# C-metr_digital.net
KiCad netlist of a schematic drawn in Altium Designer
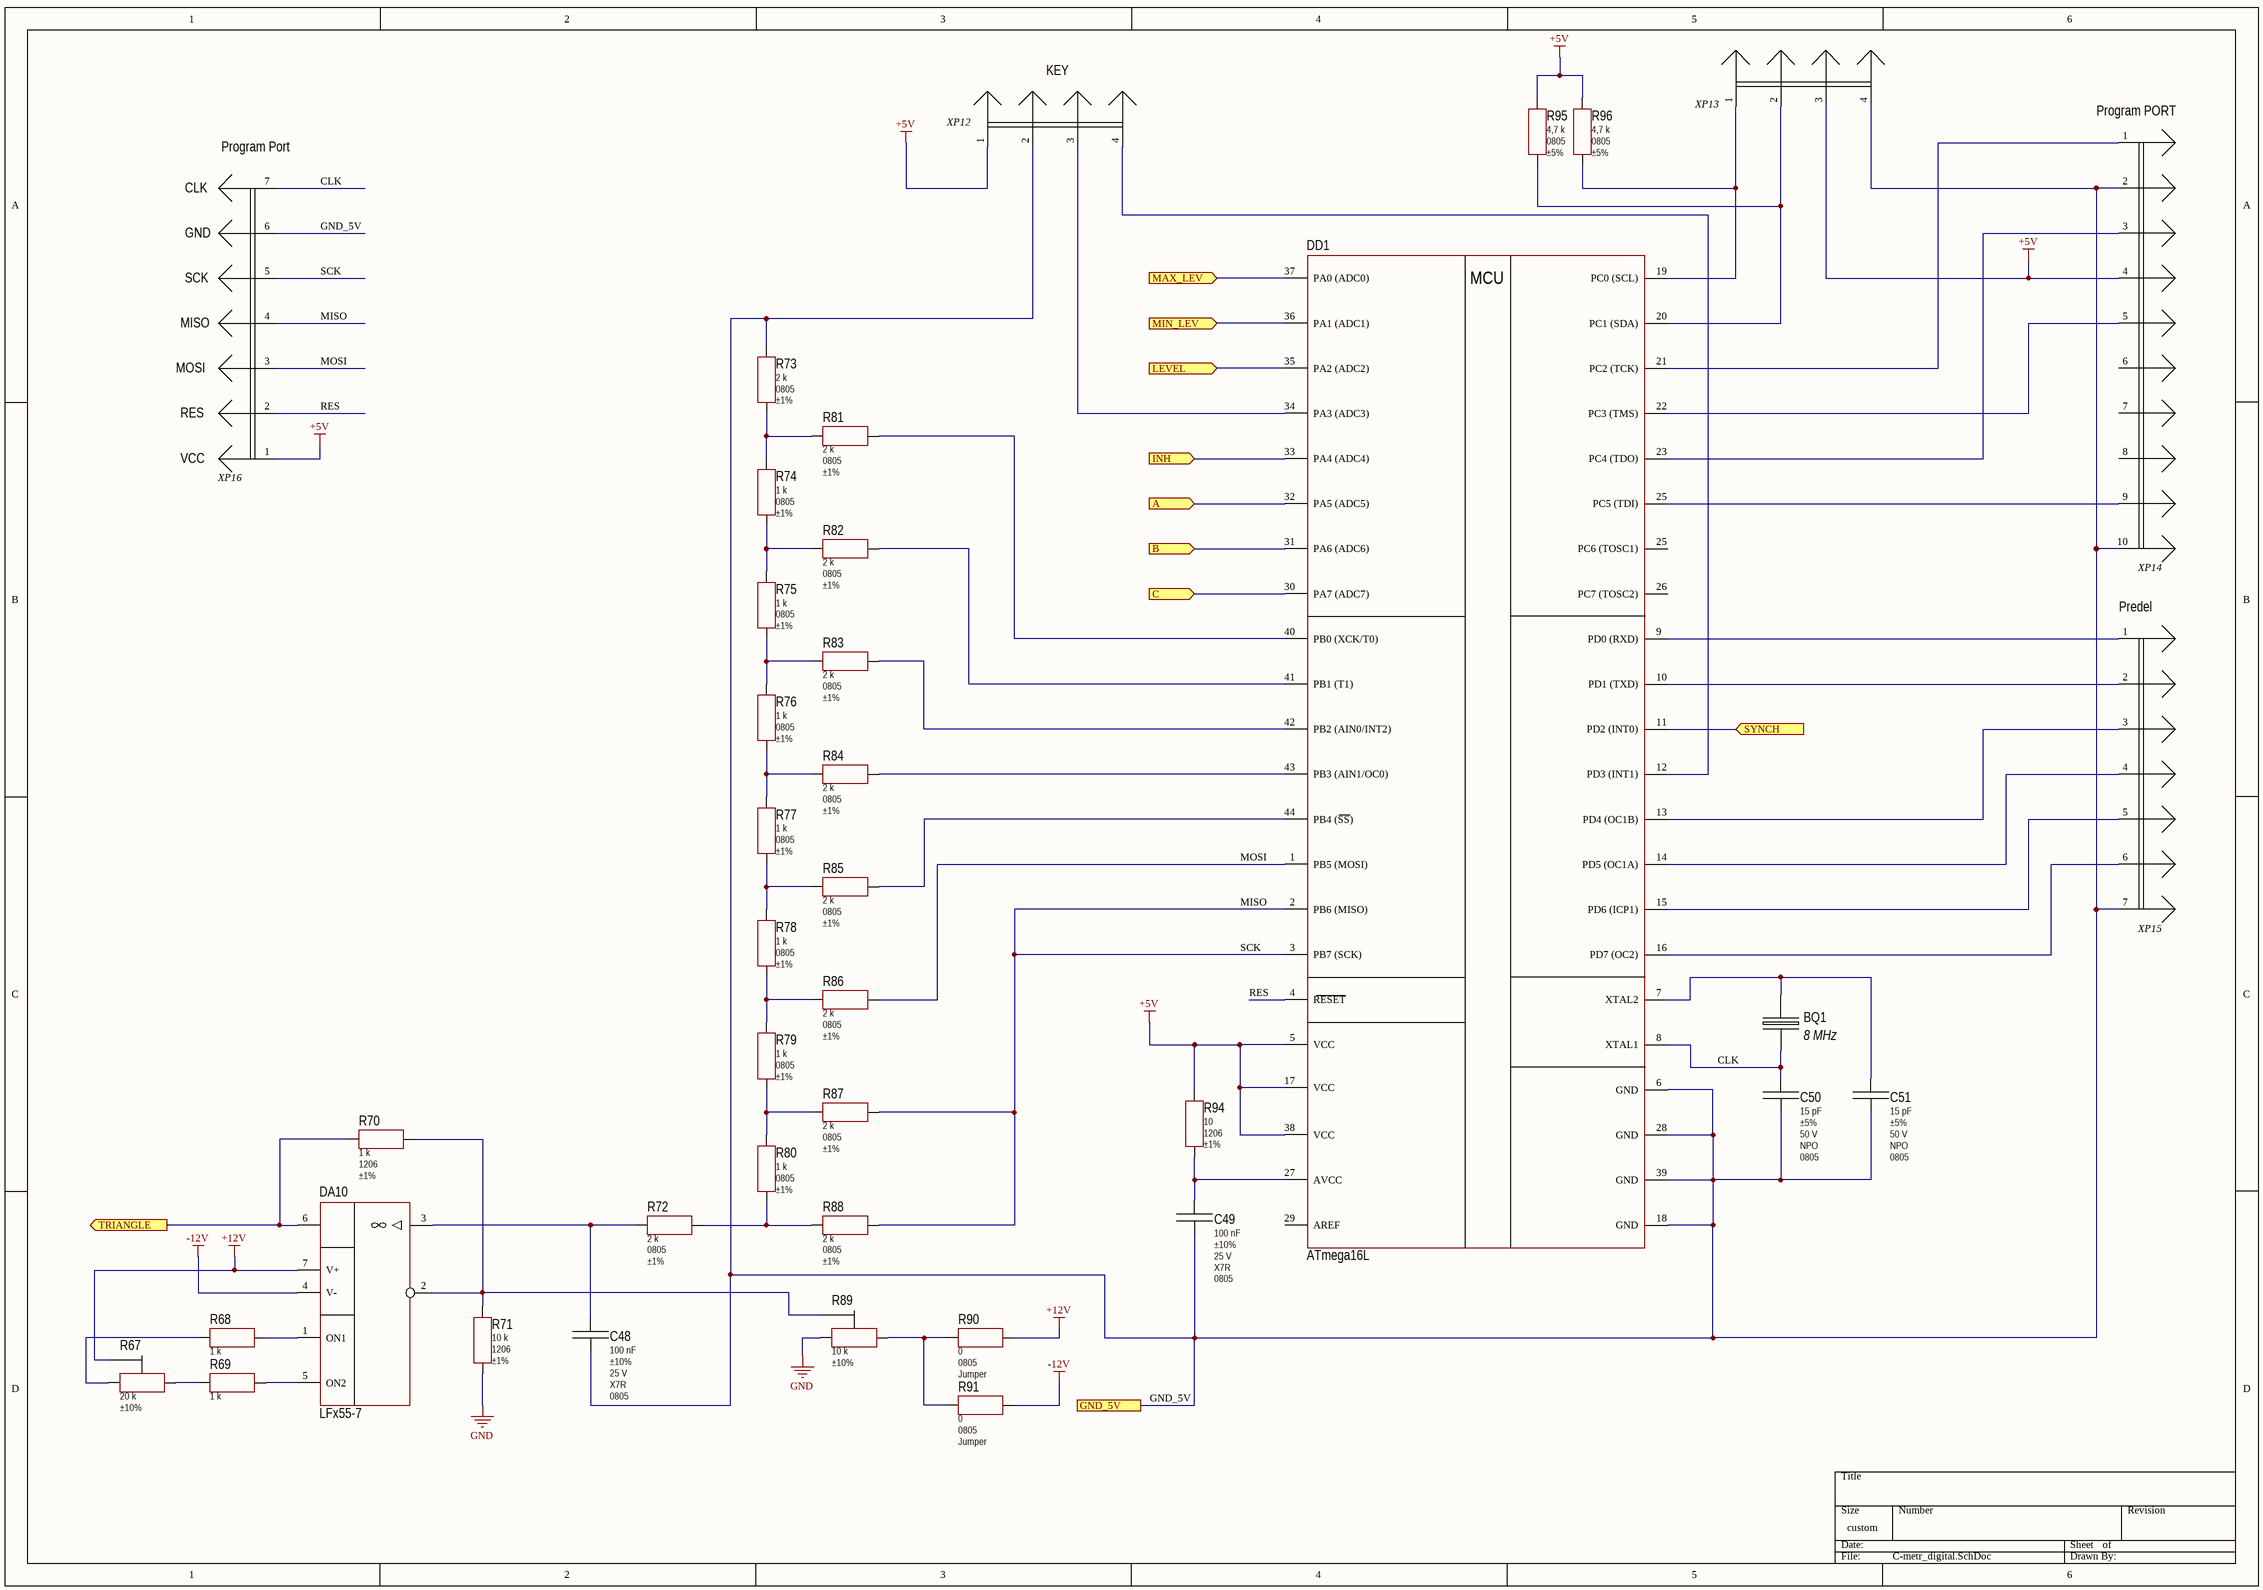
[diagram p0: C-metr_digital.SchDoc]

(export (version "E")
  (design (tool "Eeschema 10.0.6"))
  (components
    (comp (ref "BQ1")
      (value "8 MHz")
      (footprint "HC-49/U3H")
      (fields (field (name "PART NUMBER") "KX-3HT 8 MHz") (field (name "MANUFACTURER") "Geyer Electronic"))
      (libsource (lib "GOST") (part "Resonator"))
    )
    (comp (ref "C48")
      (value "100 nF")
      (footprint "C-0805-0.95")
      (fields
        (field (name "VALUESCH") "100 nF")
        (field (name "TOLERANCE") "±10%")
        (field (name "VOLTAGE") "25 V")
        (field (name "DIELECTRIC") "X7R")
        (field (name "CASE") "0805")
        (field (name "PART NUMBER") "CC0805KRX7R8BB104")
        (field (name "MANUFACTURER") "Yageo")
      )
      (libsource (lib "GOST") (part "Capacitor"))
    )
    (comp (ref "C49")
      (value "100 nF")
      (footprint "C-0805-0.95")
      (fields
        (field (name "VALUESCH") "100 nF")
        (field (name "TOLERANCE") "±10%")
        (field (name "VOLTAGE") "25 V")
        (field (name "DIELECTRIC") "X7R")
        (field (name "CASE") "0805")
        (field (name "PART NUMBER") "CC0805KRX7R8BB104")
        (field (name "MANUFACTURER") "Yageo")
      )
      (libsource (lib "GOST") (part "Capacitor"))
    )
    (comp (ref "C50")
      (value "15 pF")
      (footprint "C-0805-0.7")
      (fields
        (field (name "VALUESCH") "15 pF")
        (field (name "TOLERANCE") "±5%")
        (field (name "VOLTAGE") "50 V")
        (field (name "DIELECTRIC") "NPO")
        (field (name "CASE") "0805")
        (field (name "PART NUMBER") "CC0805JRNPO9BN150")
        (field (name "MANUFACTURER") "Yageo")
      )
      (libsource (lib "GOST") (part "Capacitor"))
    )
    (comp (ref "C51")
      (value "15 pF")
      (footprint "C-0805-0.7")
      (fields
        (field (name "VALUESCH") "15 pF")
        (field (name "TOLERANCE") "±5%")
        (field (name "VOLTAGE") "50 V")
        (field (name "DIELECTRIC") "NPO")
        (field (name "CASE") "0805")
        (field (name "PART NUMBER") "CC0805JRNPO9BN150")
        (field (name "MANUFACTURER") "Yageo")
      )
      (libsource (lib "GOST") (part "Capacitor"))
    )
    (comp (ref "DA10")
      (value "LFx55-7")
      (footprint "DIP-8")
      (fields (field (name "PART NUMBER") "LF357N") (field (name "MANUFACTURER") "STMicroelectronics"))
      (libsource (lib "GOST") (part "LFx55-7"))
    )
    (comp (ref "DD1")
      (value "ATmega16L")
      (footprint "TQFP-44")
      (fields
        (field (name "PART NUMBER") "ATmega16L-8AU")
        (field (name "MANUFACTURER") "Microchip Technology")
      )
      (libsource (lib "GOST") (part "ATmega16L-8AU"))
    )
    (comp (ref "R67")
      (value "20 k")
      (footprint "3296W")
      (fields
        (field (name "VALUESCH") "20 k")
        (field (name "TOLERANCE") "±10%")
        (field (name "PART NUMBER") "3296W-1-203LF")
        (field (name "POWER") "0,5 W")
        (field (name "MANUFACTURER") "Bourns Inc.")
      )
      (libsource (lib "GOST") (part "Resistor-ADJ"))
    )
    (comp (ref "R68")
      (value "1 k")
      (footprint "R-1206")
      (fields
        (field (name "VALUESCH") "1 k")
        (field (name "TOLERANCE") "±5%")
        (field (name "PART NUMBER") "CRCW12061K00JNEA")
        (field (name "POWER") "0,25 W")
      )
      (libsource (lib "") (part "Resistor_1"))
    )
    (comp (ref "R69")
      (value "1 k")
      (footprint "R-1206")
      (fields
        (field (name "VALUESCH") "1 k")
        (field (name "TOLERANCE") "±5%")
        (field (name "PART NUMBER") "CRCW12061K00JNEA")
        (field (name "POWER") "0,25 W")
      )
      (libsource (lib "") (part "Resistor_1"))
    )
    (comp (ref "R70")
      (value "1 k")
      (footprint "R-1206")
      (fields
        (field (name "VALUESCH") "1 k")
        (field (name "CASE") "1206")
        (field (name "TOLERANCE") "±1%")
        (field (name "PART NUMBER") "CRCW12061K00FKEA")
        (field (name "POWER") "0,25 W")
        (field (name "MANUFACTURER") "Vishay Dale")
      )
      (libsource (lib "") (part "Resistor_2"))
    )
    (comp (ref "R71")
      (value "10 k")
      (footprint "R-1206")
      (fields
        (field (name "VALUESCH") "10 k")
        (field (name "CASE") "1206")
        (field (name "TOLERANCE") "±1%")
        (field (name "PART NUMBER") "CRCW120610K0FKEA")
        (field (name "POWER") "0,25 W")
        (field (name "MANUFACTURER") "Vishay Dale")
      )
      (libsource (lib "GOST") (part "Resistor"))
    )
    (comp (ref "R72")
      (value "2 k")
      (footprint "R-0805")
      (fields
        (field (name "VALUESCH") "2 k")
        (field (name "CASE") "0805")
        (field (name "TOLERANCE") "±1%")
        (field (name "PART NUMBER") "CRCW08052K00FKEA")
        (field (name "POWER") "0,125 W")
        (field (name "MANUFACTURER") "Vishay Dale")
      )
      (libsource (lib "") (part "Resistor_2"))
    )
    (comp (ref "R73")
      (value "2 k")
      (footprint "R-0805")
      (fields
        (field (name "VALUESCH") "2 k")
        (field (name "CASE") "0805")
        (field (name "TOLERANCE") "±1%")
        (field (name "PART NUMBER") "CRCW08052K00FKEA")
        (field (name "POWER") "0,125 W")
        (field (name "MANUFACTURER") "Vishay Dale")
      )
      (libsource (lib "") (part "Resistor_1"))
    )
    (comp (ref "R74")
      (value "1 k")
      (footprint "R-0805")
      (fields
        (field (name "VALUESCH") "1 k")
        (field (name "CASE") "0805")
        (field (name "TOLERANCE") "±1%")
        (field (name "PART NUMBER") "CRCW08051K00FKEA")
        (field (name "POWER") "0,125 W")
        (field (name "MANUFACTURER") "Vishay Dale")
      )
      (libsource (lib "GOST") (part "Resistor"))
    )
    (comp (ref "R75")
      (value "1 k")
      (footprint "R-0805")
      (fields
        (field (name "VALUESCH") "1 k")
        (field (name "CASE") "0805")
        (field (name "TOLERANCE") "±1%")
        (field (name "PART NUMBER") "CRCW08051K00FKEA")
        (field (name "POWER") "0,125 W")
        (field (name "MANUFACTURER") "Vishay Dale")
      )
      (libsource (lib "GOST") (part "Resistor"))
    )
    (comp (ref "R76")
      (value "1 k")
      (footprint "R-0805")
      (fields
        (field (name "VALUESCH") "1 k")
        (field (name "CASE") "0805")
        (field (name "TOLERANCE") "±1%")
        (field (name "PART NUMBER") "CRCW08051K00FKEA")
        (field (name "POWER") "0,125 W")
        (field (name "MANUFACTURER") "Vishay Dale")
      )
      (libsource (lib "GOST") (part "Resistor"))
    )
    (comp (ref "R77")
      (value "1 k")
      (footprint "R-0805")
      (fields
        (field (name "VALUESCH") "1 k")
        (field (name "CASE") "0805")
        (field (name "TOLERANCE") "±1%")
        (field (name "PART NUMBER") "CRCW08051K00FKEA")
        (field (name "POWER") "0,125 W")
        (field (name "MANUFACTURER") "Vishay Dale")
      )
      (libsource (lib "GOST") (part "Resistor"))
    )
    (comp (ref "R78")
      (value "1 k")
      (footprint "R-0805")
      (fields
        (field (name "VALUESCH") "1 k")
        (field (name "CASE") "0805")
        (field (name "TOLERANCE") "±1%")
        (field (name "PART NUMBER") "CRCW08051K00FKEA")
        (field (name "POWER") "0,125 W")
        (field (name "MANUFACTURER") "Vishay Dale")
      )
      (libsource (lib "GOST") (part "Resistor"))
    )
    (comp (ref "R79")
      (value "1 k")
      (footprint "R-0805")
      (fields
        (field (name "VALUESCH") "1 k")
        (field (name "CASE") "0805")
        (field (name "TOLERANCE") "±1%")
        (field (name "PART NUMBER") "CRCW08051K00FKEA")
        (field (name "POWER") "0,125 W")
        (field (name "MANUFACTURER") "Vishay Dale")
      )
      (libsource (lib "GOST") (part "Resistor"))
    )
    (comp (ref "R80")
      (value "1 k")
      (footprint "R-0805")
      (fields
        (field (name "VALUESCH") "1 k")
        (field (name "CASE") "0805")
        (field (name "TOLERANCE") "±1%")
        (field (name "PART NUMBER") "CRCW08051K00FKEA")
        (field (name "POWER") "0,125 W")
        (field (name "MANUFACTURER") "Vishay Dale")
      )
      (libsource (lib "GOST") (part "Resistor"))
    )
    (comp (ref "R81")
      (value "2 k")
      (footprint "R-0805")
      (fields
        (field (name "VALUESCH") "2 k")
        (field (name "CASE") "0805")
        (field (name "TOLERANCE") "±1%")
        (field (name "PART NUMBER") "CRCW08052K00FKEA")
        (field (name "POWER") "0,125 W")
        (field (name "MANUFACTURER") "Vishay Dale")
      )
      (libsource (lib "") (part "Resistor_2"))
    )
    (comp (ref "R82")
      (value "2 k")
      (footprint "R-0805")
      (fields
        (field (name "VALUESCH") "2 k")
        (field (name "CASE") "0805")
        (field (name "TOLERANCE") "±1%")
        (field (name "PART NUMBER") "CRCW08052K00FKEA")
        (field (name "POWER") "0,125 W")
        (field (name "MANUFACTURER") "Vishay Dale")
      )
      (libsource (lib "") (part "Resistor_2"))
    )
    (comp (ref "R83")
      (value "2 k")
      (footprint "R-0805")
      (fields
        (field (name "VALUESCH") "2 k")
        (field (name "CASE") "0805")
        (field (name "TOLERANCE") "±1%")
        (field (name "PART NUMBER") "CRCW08052K00FKEA")
        (field (name "POWER") "0,125 W")
        (field (name "MANUFACTURER") "Vishay Dale")
      )
      (libsource (lib "") (part "Resistor_2"))
    )
    (comp (ref "R84")
      (value "2 k")
      (footprint "R-0805")
      (fields
        (field (name "VALUESCH") "2 k")
        (field (name "CASE") "0805")
        (field (name "TOLERANCE") "±1%")
        (field (name "PART NUMBER") "CRCW08052K00FKEA")
        (field (name "POWER") "0,125 W")
        (field (name "MANUFACTURER") "Vishay Dale")
      )
      (libsource (lib "") (part "Resistor_2"))
    )
    (comp (ref "R85")
      (value "2 k")
      (footprint "R-0805")
      (fields
        (field (name "VALUESCH") "2 k")
        (field (name "CASE") "0805")
        (field (name "TOLERANCE") "±1%")
        (field (name "PART NUMBER") "CRCW08052K00FKEA")
        (field (name "POWER") "0,125 W")
        (field (name "MANUFACTURER") "Vishay Dale")
      )
      (libsource (lib "") (part "Resistor_2"))
    )
    (comp (ref "R86")
      (value "2 k")
      (footprint "R-0805")
      (fields
        (field (name "VALUESCH") "2 k")
        (field (name "CASE") "0805")
        (field (name "TOLERANCE") "±1%")
        (field (name "PART NUMBER") "CRCW08052K00FKEA")
        (field (name "POWER") "0,125 W")
        (field (name "MANUFACTURER") "Vishay Dale")
      )
      (libsource (lib "") (part "Resistor_2"))
    )
    (comp (ref "R87")
      (value "2 k")
      (footprint "R-0805")
      (fields
        (field (name "VALUESCH") "2 k")
        (field (name "CASE") "0805")
        (field (name "TOLERANCE") "±1%")
        (field (name "PART NUMBER") "CRCW08052K00FKEA")
        (field (name "POWER") "0,125 W")
        (field (name "MANUFACTURER") "Vishay Dale")
      )
      (libsource (lib "") (part "Resistor_2"))
    )
    (comp (ref "R88")
      (value "2 k")
      (footprint "R-0805")
      (fields
        (field (name "VALUESCH") "2 k")
        (field (name "CASE") "0805")
        (field (name "TOLERANCE") "±1%")
        (field (name "PART NUMBER") "CRCW08052K00FKEA")
        (field (name "POWER") "0,125 W")
        (field (name "MANUFACTURER") "Vishay Dale")
      )
      (libsource (lib "") (part "Resistor_2"))
    )
    (comp (ref "R89")
      (value "10 k")
      (footprint "3296W")
      (fields
        (field (name "VALUESCH") "10 k")
        (field (name "TOLERANCE") "±10%")
        (field (name "PART NUMBER") "3296W-1-103LF")
        (field (name "POWER") "0,5 W")
        (field (name "MANUFACTURER") "Bourns Inc.")
      )
      (libsource (lib "GOST") (part "Resistor-ADJ"))
    )
    (comp (ref "R90")
      (value "0")
      (footprint "R-0805")
      (fields
        (field (name "VALUESCH") "0")
        (field (name "CASE") "0805")
        (field (name "TOLERANCE") "Jumper")
        (field (name "PART NUMBER") "CRCW08050000Z0EA")
        (field (name "POWER") "0,125 W")
        (field (name "MANUFACTURER") "Vishay Dale")
      )
      (libsource (lib "") (part "Resistor_1"))
    )
    (comp (ref "R91")
      (value "0")
      (footprint "R-0805")
      (fields
        (field (name "VALUESCH") "0")
        (field (name "CASE") "0805")
        (field (name "TOLERANCE") "Jumper")
        (field (name "PART NUMBER") "CRCW08050000Z0EA")
        (field (name "POWER") "0,125 W")
        (field (name "MANUFACTURER") "Vishay Dale")
      )
      (libsource (lib "") (part "Resistor_1"))
    )
    (comp (ref "R94")
      (value "10")
      (footprint "R-1206")
      (fields
        (field (name "VALUESCH") "10")
        (field (name "CASE") "1206")
        (field (name "TOLERANCE") "±1%")
        (field (name "PART NUMBER") "CRCW120610R0FKEA")
        (field (name "POWER") "0,25 W")
        (field (name "MANUFACTURER") "Vishay Dale")
      )
      (libsource (lib "GOST") (part "Resistor"))
    )
    (comp (ref "R95")
      (value "4,7 k")
      (footprint "R-0805")
      (fields
        (field (name "VALUESCH") "4,7 k")
        (field (name "CASE") "0805")
        (field (name "TOLERANCE") "±5%")
        (field (name "PART NUMBER") "CRCW08054K70JNEA")
        (field (name "POWER") "0,125 W")
        (field (name "MANUFACTURER") "Vishay Dale")
      )
      (libsource (lib "GOST") (part "Resistor"))
    )
    (comp (ref "R96")
      (value "4,7 k")
      (footprint "R-0805")
      (fields
        (field (name "VALUESCH") "4,7 k")
        (field (name "CASE") "0805")
        (field (name "TOLERANCE") "±5%")
        (field (name "PART NUMBER") "CRCW08054K70JNEA")
        (field (name "POWER") "0,125 W")
        (field (name "MANUFACTURER") "Vishay Dale")
      )
      (libsource (lib "GOST") (part "Resistor"))
    )
    (comp (ref "XP12")
      (value "Text")
      (footprint "61300411121")
      (fields (field (name "PART NUMBER") "61300411121") (field (name "MANUFACTURER") "Würth Elektronik"))
      (libsource (lib "GOST") (part "Con-4-M"))
    )
    (comp (ref "XP13")
      (value "Text")
      (footprint "61300411121")
      (fields (field (name "PART NUMBER") "61300411121") (field (name "MANUFACTURER") "Würth Elektronik"))
      (libsource (lib "GOST") (part "Con-4-M"))
    )
    (comp (ref "XP14")
      (value "Text")
      (footprint "61201021621")
      (fields (field (name "PART NUMBER") "61201021621") (field (name "MANUFACTURER") "Würth Elektronik"))
      (libsource (lib "GOST") (part "Con-10-M"))
    )
    (comp (ref "XP15")
      (value "Text")
      (footprint "61300711121")
      (fields (field (name "PART NUMBER") "61300711121") (field (name "MANUFACTURER") "Würth Elektronik"))
      (libsource (lib "GOST") (part "Con-7-M"))
    )
    (comp (ref "XP16")
      (value "Text")
      (footprint "61300711121")
      (fields (field (name "PART NUMBER") "61300711121") (field (name "MANUFACTURER") "Würth Elektronik"))
      (libsource (lib "GOST") (part "Con-7-M"))
    )
  )
  (nets
    (net (code "1") (name "+5V") (class "Default")
      (node (ref "DD1") (pin "17") (pinfunction "VCC_17") (pintype "power_in"))
      (node (ref "DD1") (pin "38") (pinfunction "VCC_38") (pintype "power_in"))
      (node (ref "DD1") (pin "5") (pinfunction "VCC_5") (pintype "power_in"))
      (node (ref "R94") (pin "2") (pinfunction "2_2") (pintype "passive"))
      (node (ref "R95") (pin "2") (pinfunction "2_2") (pintype "passive"))
      (node (ref "R96") (pin "2") (pinfunction "2_2") (pintype "passive"))
      (node (ref "XP12") (pin "1") (pintype "passive"))
      (node (ref "XP13") (pin "3") (pintype "passive"))
      (node (ref "XP14") (pin "4") (pintype "passive"))
      (node (ref "XP16") (pin "1") (pintype "passive"))
    )
    (net (code "2") (name "+12V") (class "Default")
      (node (ref "DA10") (pin "7") (pinfunction "V+_7") (pintype "passive"))
      (node (ref "R67") (pin "2") (pinfunction "2_2") (pintype "passive"))
      (node (ref "R90") (pin "1") (pinfunction "1_1") (pintype "passive"))
    )
    (net (code "3") (name "-12V") (class "Default")
      (node (ref "DA10") (pin "4") (pinfunction "V-_4") (pintype "passive"))
      (node (ref "R91") (pin "1") (pinfunction "1_1") (pintype "passive"))
    )
    (net (code "4") (name "/A") (class "Default")
      (node (ref "DD1") (pin "32") (pinfunction "PA5_(ADC5)_32") (pintype "passive"))
    )
    (net (code "5") (name "/B") (class "Default")
      (node (ref "DD1") (pin "31") (pinfunction "PA6_(ADC6)_31") (pintype "passive"))
    )
    (net (code "6") (name "/C") (class "Default")
      (node (ref "DD1") (pin "30") (pinfunction "PA7_(ADC7)_30") (pintype "passive"))
    )
    (net (code "7") (name "/CLK") (class "Default")
      (node (ref "BQ1") (pin "1") (pinfunction "1_1") (pintype "passive"))
      (node (ref "C50") (pin "2") (pinfunction "2_2") (pintype "power_in"))
      (node (ref "DD1") (pin "8") (pinfunction "XTAL1_8") (pintype "power_in"))
      (node (ref "XP16") (pin "7") (pintype "passive"))
    )
    (net (code "8") (name "/GND_5V") (class "Default")
      (node (ref "C48") (pin "1") (pinfunction "1_1") (pintype "power_in"))
      (node (ref "C49") (pin "1") (pinfunction "1_1") (pintype "power_in"))
      (node (ref "C50") (pin "1") (pinfunction "1_1") (pintype "power_in"))
      (node (ref "C51") (pin "1") (pinfunction "1_1") (pintype "power_in"))
      (node (ref "DD1") (pin "18") (pinfunction "GND_18") (pintype "power_in"))
      (node (ref "DD1") (pin "28") (pinfunction "GND_28") (pintype "power_in"))
      (node (ref "DD1") (pin "39") (pinfunction "GND_39") (pintype "power_in"))
      (node (ref "DD1") (pin "6") (pinfunction "GND_6") (pintype "power_in"))
      (node (ref "R73") (pin "1") (pinfunction "1_1") (pintype "passive"))
      (node (ref "XP12") (pin "2") (pintype "passive"))
      (node (ref "XP13") (pin "4") (pintype "passive"))
      (node (ref "XP14") (pin "10") (pintype "passive"))
      (node (ref "XP14") (pin "2") (pintype "passive"))
      (node (ref "XP15") (pin "7") (pintype "passive"))
      (node (ref "XP16") (pin "6") (pintype "passive"))
    )
    (net (code "9") (name "/INH") (class "Default")
      (node (ref "DD1") (pin "33") (pinfunction "PA4_(ADC4)_33") (pintype "passive"))
    )
    (net (code "10") (name "/LEVEL") (class "Default")
      (node (ref "DD1") (pin "35") (pinfunction "PA2_(ADC2)_35") (pintype "passive"))
    )
    (net (code "11") (name "/MAX_LEV") (class "Default")
      (node (ref "DD1") (pin "37") (pinfunction "PA0_(ADC0)_37") (pintype "passive"))
    )
    (net (code "12") (name "/MIN_LEV") (class "Default")
      (node (ref "DD1") (pin "36") (pinfunction "PA1_(ADC1)_36") (pintype "passive"))
    )
    (net (code "13") (name "/MISO") (class "Default")
      (node (ref "DD1") (pin "2") (pinfunction "PB6_(MISO)_2") (pintype "passive"))
      (node (ref "DD1") (pin "3") (pinfunction "PB7_(SCK)_3") (pintype "passive"))
      (node (ref "R87") (pin "2") (pinfunction "2_2") (pintype "passive"))
      (node (ref "R88") (pin "2") (pinfunction "2_2") (pintype "passive"))
      (node (ref "XP16") (pin "4") (pintype "passive"))
      (node (ref "XP16") (pin "5") (pintype "passive"))
    )
    (net (code "14") (name "/MOSI") (class "Default")
      (node (ref "DD1") (pin "1") (pinfunction "PB5_(MOSI)_1") (pintype "passive"))
      (node (ref "R86") (pin "2") (pinfunction "2_2") (pintype "passive"))
      (node (ref "XP16") (pin "3") (pintype "passive"))
    )
    (net (code "15") (name "/RES") (class "Default")
      (node (ref "DD1") (pin "4") (pinfunction "RESET_4") (pintype "passive"))
      (node (ref "XP16") (pin "2") (pintype "passive"))
    )
    (net (code "16") (name "/SYNCH") (class "Default")
      (node (ref "DD1") (pin "11") (pinfunction "PD2_(INT0)_11") (pintype "passive"))
    )
    (net (code "17") (name "/TRIANGLE") (class "Default")
      (node (ref "DA10") (pin "6") (pinfunction "OUT_6") (pintype "passive"))
      (node (ref "R70") (pin "1") (pinfunction "1_1") (pintype "passive"))
    )
    (net (code "18") (name "GND") (class "Default")
      (node (ref "R71") (pin "1") (pinfunction "1_1") (pintype "passive"))
      (node (ref "R89") (pin "3") (pinfunction "3_3") (pintype "passive"))
    )
    (net (code "19") (name "Net-(DA10-+IN)") (class "Default")
      (node (ref "C48") (pin "2") (pinfunction "2_2") (pintype "power_in"))
      (node (ref "DA10") (pin "3") (pinfunction "+IN_3") (pintype "passive"))
      (node (ref "R72") (pin "1") (pinfunction "1_1") (pintype "passive"))
    )
    (net (code "20") (name "Net-(DA10--IN)") (class "Default")
      (node (ref "DA10") (pin "2") (pinfunction "-IN_2") (pintype "passive"))
      (node (ref "R70") (pin "2") (pinfunction "2_2") (pintype "passive"))
      (node (ref "R71") (pin "2") (pinfunction "2_2") (pintype "passive"))
      (node (ref "R89") (pin "2") (pinfunction "2_2") (pintype "passive"))
    )
    (net (code "21") (name "Net-(DA10-ON1)") (class "Default")
      (node (ref "DA10") (pin "1") (pinfunction "ON1_1") (pintype "passive"))
      (node (ref "R68") (pin "1") (pinfunction "1_1") (pintype "passive"))
    )
    (net (code "22") (name "Net-(DA10-ON2)") (class "Default")
      (node (ref "DA10") (pin "5") (pinfunction "ON2_5") (pintype "passive"))
      (node (ref "R69") (pin "1") (pinfunction "1_1") (pintype "passive"))
    )
    (net (code "23") (name "Net-(DD1-AVCC)") (class "Default")
      (node (ref "C49") (pin "2") (pinfunction "2_2") (pintype "power_in"))
      (node (ref "DD1") (pin "27") (pinfunction "AVCC_27") (pintype "power_in"))
      (node (ref "R94") (pin "1") (pinfunction "1_1") (pintype "passive"))
    )
    (net (code "24") (name "Net-(DD1-PA3_(ADC3))") (class "Default")
      (node (ref "DD1") (pin "34") (pinfunction "PA3_(ADC3)_34") (pintype "passive"))
      (node (ref "XP12") (pin "3") (pintype "passive"))
    )
    (net (code "25") (name "Net-(DD1-PB0_(XCK{slash}T0))") (class "Default")
      (node (ref "DD1") (pin "40") (pinfunction "PB0_(XCK/T0)_40") (pintype "passive"))
      (node (ref "R81") (pin "2") (pinfunction "2_2") (pintype "passive"))
    )
    (net (code "26") (name "Net-(DD1-PB1_(T1))") (class "Default")
      (node (ref "DD1") (pin "41") (pinfunction "PB1_(T1)_41") (pintype "passive"))
      (node (ref "R82") (pin "2") (pinfunction "2_2") (pintype "passive"))
    )
    (net (code "27") (name "Net-(DD1-PB2_(AIN0{slash}INT2))") (class "Default")
      (node (ref "DD1") (pin "42") (pinfunction "PB2_(AIN0/INT2)_42") (pintype "passive"))
      (node (ref "R83") (pin "2") (pinfunction "2_2") (pintype "passive"))
    )
    (net (code "28") (name "Net-(DD1-PB3_(AIN1{slash}OC0))") (class "Default")
      (node (ref "DD1") (pin "43") (pinfunction "PB3_(AIN1/OC0)_43") (pintype "passive"))
      (node (ref "R84") (pin "2") (pinfunction "2_2") (pintype "passive"))
    )
    (net (code "29") (name "Net-(DD1-PB4_(SS))") (class "Default")
      (node (ref "DD1") (pin "44") (pinfunction "PB4_(SS)_44") (pintype "passive"))
      (node (ref "R85") (pin "2") (pinfunction "2_2") (pintype "passive"))
    )
    (net (code "30") (name "Net-(DD1-PC0_(SCL))") (class "Default")
      (node (ref "DD1") (pin "19") (pinfunction "PC0_(SCL)_19") (pintype "passive"))
      (node (ref "R96") (pin "1") (pinfunction "1_1") (pintype "passive"))
      (node (ref "XP13") (pin "1") (pintype "passive"))
    )
    (net (code "31") (name "Net-(DD1-PC1_(SDA))") (class "Default")
      (node (ref "DD1") (pin "20") (pinfunction "PC1_(SDA)_20") (pintype "passive"))
      (node (ref "R95") (pin "1") (pinfunction "1_1") (pintype "passive"))
      (node (ref "XP13") (pin "2") (pintype "passive"))
    )
    (net (code "32") (name "Net-(DD1-PC2_(TCK))") (class "Default")
      (node (ref "DD1") (pin "21") (pinfunction "PC2_(TCK)_21") (pintype "passive"))
      (node (ref "XP14") (pin "1") (pintype "passive"))
    )
    (net (code "33") (name "Net-(DD1-PC3_(TMS))") (class "Default")
      (node (ref "DD1") (pin "22") (pinfunction "PC3_(TMS)_22") (pintype "passive"))
      (node (ref "XP14") (pin "5") (pintype "passive"))
    )
    (net (code "34") (name "Net-(DD1-PC4_(TDO))") (class "Default")
      (node (ref "DD1") (pin "23") (pinfunction "PC4_(TDO)_23") (pintype "passive"))
      (node (ref "XP14") (pin "3") (pintype "passive"))
    )
    (net (code "35") (name "Net-(DD1-PC5_(TDI))") (class "Default")
      (node (ref "DD1") (pin "25") (pinfunction "PC5_(TDI)_25") (pintype "passive"))
      (node (ref "XP14") (pin "9") (pintype "passive"))
    )
    (net (code "36") (name "Net-(DD1-PD0_(RXD))") (class "Default")
      (node (ref "DD1") (pin "9") (pinfunction "PD0_(RXD)_9") (pintype "passive"))
      (node (ref "XP15") (pin "1") (pintype "passive"))
    )
    (net (code "37") (name "Net-(DD1-PD1_(TXD))") (class "Default")
      (node (ref "DD1") (pin "10") (pinfunction "PD1_(TXD)_10") (pintype "passive"))
      (node (ref "XP15") (pin "2") (pintype "passive"))
    )
    (net (code "38") (name "Net-(DD1-PD3_(INT1))") (class "Default")
      (node (ref "DD1") (pin "12") (pinfunction "PD3_(INT1)_12") (pintype "passive"))
      (node (ref "XP12") (pin "4") (pintype "passive"))
    )
    (net (code "39") (name "Net-(DD1-PD4_(OC1B))") (class "Default")
      (node (ref "DD1") (pin "13") (pinfunction "PD4_(OC1B)_13") (pintype "passive"))
      (node (ref "XP15") (pin "3") (pintype "passive"))
    )
    (net (code "40") (name "Net-(DD1-PD5_(OC1A))") (class "Default")
      (node (ref "DD1") (pin "14") (pinfunction "PD5_(OC1A)_14") (pintype "passive"))
      (node (ref "XP15") (pin "4") (pintype "passive"))
    )
    (net (code "41") (name "Net-(DD1-PD6_(ICP1))") (class "Default")
      (node (ref "DD1") (pin "15") (pinfunction "PD6_(ICP1)_15") (pintype "passive"))
      (node (ref "XP15") (pin "5") (pintype "passive"))
    )
    (net (code "42") (name "Net-(DD1-PD7_(OC2))") (class "Default")
      (node (ref "DD1") (pin "16") (pinfunction "PD7_(OC2)_16") (pintype "passive"))
      (node (ref "XP15") (pin "6") (pintype "passive"))
    )
    (net (code "43") (name "Net-(DD1-XTAL2)") (class "Default")
      (node (ref "BQ1") (pin "2") (pinfunction "2_2") (pintype "passive"))
      (node (ref "C51") (pin "2") (pinfunction "2_2") (pintype "power_in"))
      (node (ref "DD1") (pin "7") (pinfunction "XTAL2_7") (pintype "power_in"))
    )
    (net (code "44") (name "Net-(R67-Pad1)") (class "Default")
      (node (ref "R67") (pin "1") (pinfunction "1_1") (pintype "passive"))
      (node (ref "R69") (pin "2") (pinfunction "2_2") (pintype "passive"))
    )
    (net (code "45") (name "Net-(R67-Pad3)") (class "Default")
      (node (ref "R67") (pin "3") (pinfunction "3_3") (pintype "passive"))
      (node (ref "R68") (pin "2") (pinfunction "2_2") (pintype "passive"))
    )
    (net (code "46") (name "Net-(R72-Pad2)") (class "Default")
      (node (ref "R72") (pin "2") (pinfunction "2_2") (pintype "passive"))
      (node (ref "R80") (pin "1") (pinfunction "1_1") (pintype "passive"))
      (node (ref "R88") (pin "1") (pinfunction "1_1") (pintype "passive"))
    )
    (net (code "47") (name "Net-(R73-Pad2)") (class "Default")
      (node (ref "R73") (pin "2") (pinfunction "2_2") (pintype "passive"))
      (node (ref "R74") (pin "2") (pinfunction "2_2") (pintype "passive"))
      (node (ref "R81") (pin "1") (pinfunction "1_1") (pintype "passive"))
    )
    (net (code "48") (name "Net-(R74-Pad1)") (class "Default")
      (node (ref "R74") (pin "1") (pinfunction "1_1") (pintype "passive"))
      (node (ref "R75") (pin "2") (pinfunction "2_2") (pintype "passive"))
      (node (ref "R82") (pin "1") (pinfunction "1_1") (pintype "passive"))
    )
    (net (code "49") (name "Net-(R75-Pad1)") (class "Default")
      (node (ref "R75") (pin "1") (pinfunction "1_1") (pintype "passive"))
      (node (ref "R76") (pin "2") (pinfunction "2_2") (pintype "passive"))
      (node (ref "R83") (pin "1") (pinfunction "1_1") (pintype "passive"))
    )
    (net (code "50") (name "Net-(R76-Pad1)") (class "Default")
      (node (ref "R76") (pin "1") (pinfunction "1_1") (pintype "passive"))
      (node (ref "R77") (pin "2") (pinfunction "2_2") (pintype "passive"))
      (node (ref "R84") (pin "1") (pinfunction "1_1") (pintype "passive"))
    )
    (net (code "51") (name "Net-(R77-Pad1)") (class "Default")
      (node (ref "R77") (pin "1") (pinfunction "1_1") (pintype "passive"))
      (node (ref "R78") (pin "2") (pinfunction "2_2") (pintype "passive"))
      (node (ref "R85") (pin "1") (pinfunction "1_1") (pintype "passive"))
    )
    (net (code "52") (name "Net-(R78-Pad1)") (class "Default")
      (node (ref "R78") (pin "1") (pinfunction "1_1") (pintype "passive"))
      (node (ref "R79") (pin "2") (pinfunction "2_2") (pintype "passive"))
      (node (ref "R86") (pin "1") (pinfunction "1_1") (pintype "passive"))
    )
    (net (code "53") (name "Net-(R79-Pad1)") (class "Default")
      (node (ref "R79") (pin "1") (pinfunction "1_1") (pintype "passive"))
      (node (ref "R80") (pin "2") (pinfunction "2_2") (pintype "passive"))
      (node (ref "R87") (pin "1") (pinfunction "1_1") (pintype "passive"))
    )
    (net (code "54") (name "Net-(R89-Pad1)") (class "Default")
      (node (ref "R89") (pin "1") (pinfunction "1_1") (pintype "passive"))
      (node (ref "R90") (pin "2") (pinfunction "2_2") (pintype "passive"))
      (node (ref "R91") (pin "2") (pinfunction "2_2") (pintype "passive"))
    )
    (net (code "55") (name "unconnected-(DD1-AREF-Pad29)") (class "Default")
      (node (ref "DD1") (pin "29") (pinfunction "AREF_29") (pintype "passive"))
    )
    (net (code "56") (name "unconnected-(DD1-PC6_(TOSC1)-Pad25)") (class "Default")
      (node (ref "DD1") (pin "25") (pinfunction "PC6_(TOSC1)_25") (pintype "passive"))
    )
    (net (code "57") (name "unconnected-(DD1-PC7_(TOSC2)-Pad26)") (class "Default")
      (node (ref "DD1") (pin "26") (pinfunction "PC7_(TOSC2)_26") (pintype "power_in"))
    )
    (net (code "58") (name "unconnected-(XP14-Pad6)") (class "Default")
      (node (ref "XP14") (pin "6") (pintype "passive"))
    )
    (net (code "59") (name "unconnected-(XP14-Pad7)") (class "Default")
      (node (ref "XP14") (pin "7") (pintype "passive"))
    )
    (net (code "60") (name "unconnected-(XP14-Pad8)") (class "Default")
      (node (ref "XP14") (pin "8") (pintype "passive"))
    )
  )
)
